# MotorDriver_Basic.net
KiCad netlist of a schematic drawn in EAGLE
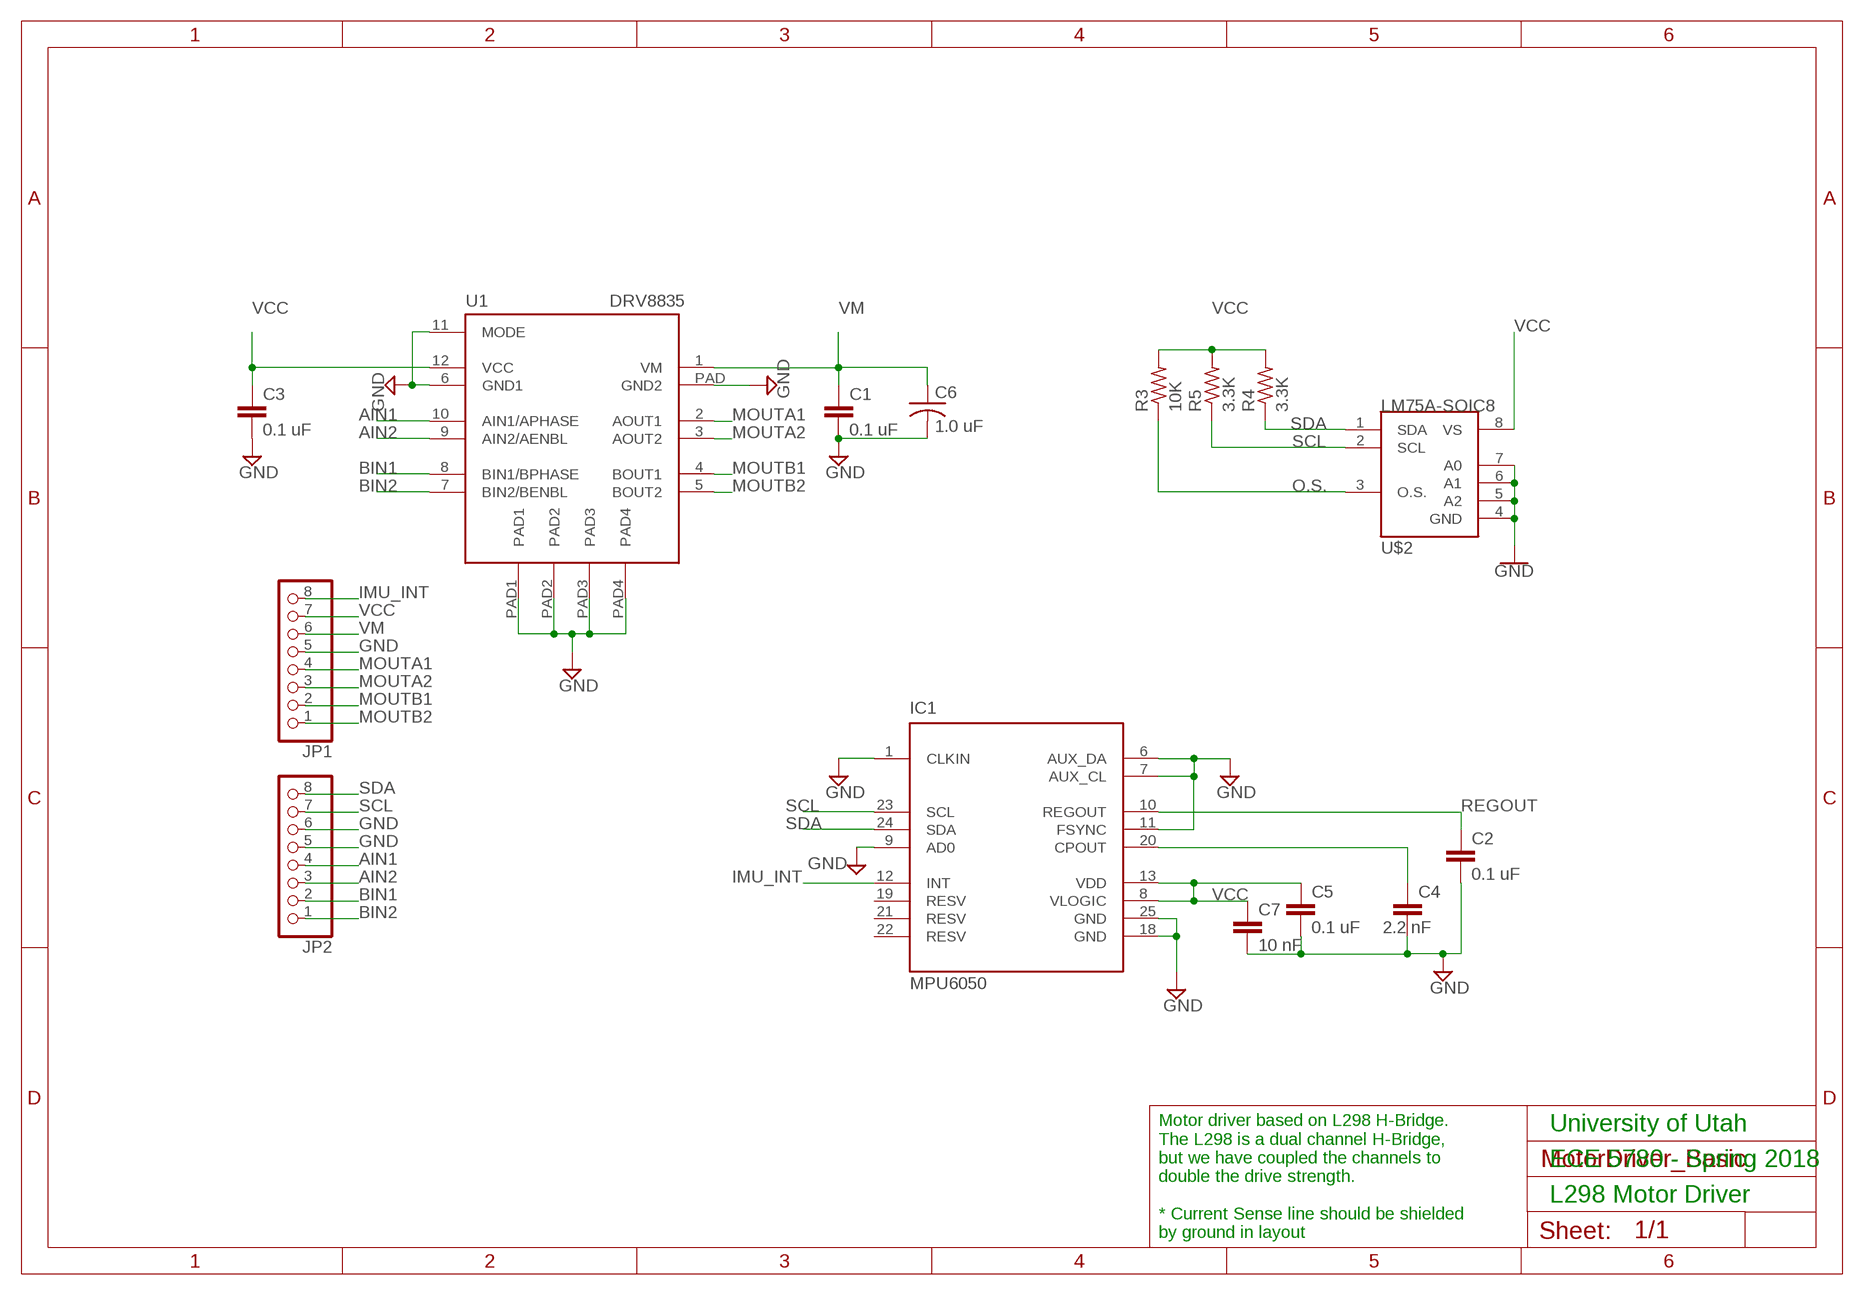
[diagram p0: schematic, sheet 1]

(export (version "E")
  (design (tool "Eeschema 10.0.6"))
  (components
    (comp (ref "C1")
      (value "0.1 uF")
      (footprint "eagle-import:C1206")
      (libsource (lib "eagle-import") (part "C-EUC1206"))
    )
    (comp (ref "C2")
      (value "0.1 uF")
      (footprint "eagle-import:C1206")
      (libsource (lib "eagle-import") (part "C-EUC1206"))
    )
    (comp (ref "C3")
      (value "0.1 uF")
      (footprint "eagle-import:C1206")
      (libsource (lib "eagle-import") (part "C-EUC1206"))
    )
    (comp (ref "C4")
      (value "2.2 nF")
      (footprint "eagle-import:C1206")
      (libsource (lib "eagle-import") (part "C-EUC1206"))
    )
    (comp (ref "C5")
      (value "0.1 uF")
      (footprint "eagle-import:C1206")
      (libsource (lib "eagle-import") (part "C-EUC1206"))
    )
    (comp (ref "C6")
      (value "1.0 uF")
      (footprint "eagle-import:C025-050X050")
      (libsource (lib "eagle-import") (part "C-US025-050X050"))
    )
    (comp (ref "C7")
      (value "10 nF")
      (footprint "eagle-import:C1206")
      (libsource (lib "eagle-import") (part "C-EUC1206"))
    )
    (comp (ref "IC1")
      (value "MPU6050")
      (footprint "eagle-import:QFN50P400X400X95-25T265X275N")
      (libsource (lib "eagle-import") (part "MPU6050"))
    )
    (comp (ref "JP1")
      (value "PINHD-1X8")
      (footprint "eagle-import:1X08")
      (libsource (lib "eagle-import") (part "PINHD-1X8"))
    )
    (comp (ref "JP2")
      (value "PINHD-1X8")
      (footprint "eagle-import:1X08")
      (libsource (lib "eagle-import") (part "PINHD-1X8"))
    )
    (comp (ref "R3")
      (value "10K")
      (footprint "eagle-import:M1206")
      (libsource (lib "eagle-import") (part "R-US_M1206"))
    )
    (comp (ref "R4")
      (value "3.3K")
      (footprint "eagle-import:M1206")
      (libsource (lib "eagle-import") (part "R-US_M1206"))
    )
    (comp (ref "R5")
      (value "3.3K")
      (footprint "eagle-import:M1206")
      (libsource (lib "eagle-import") (part "R-US_M1206"))
    )
    (comp (ref "U$2")
      (value "LM75A-SOIC8")
      (footprint "eagle-import:SOIC-8")
      (libsource (lib "eagle-import") (part "LM75A-SOIC8"))
    )
    (comp (ref "U1")
      (value "DRV8835")
      (footprint "eagle-import:WSON_2X3")
      (libsource (lib "eagle-import") (part "DRV8835"))
    )
  )
  (nets
    (net (code "1") (name "/AIN1") (class "Default")
      (node (ref "JP2") (pin "4") (pinfunction "4_4") (pintype "passive"))
      (node (ref "U1") (pin "10") (pinfunction "AIN1/APHASE_10") (pintype "bidirectional"))
    )
    (net (code "2") (name "/AIN2") (class "Default")
      (node (ref "JP2") (pin "3") (pinfunction "3_3") (pintype "passive"))
      (node (ref "U1") (pin "9") (pinfunction "AIN2/AENBL_9") (pintype "bidirectional"))
    )
    (net (code "3") (name "/BIN1") (class "Default")
      (node (ref "JP2") (pin "2") (pinfunction "2_2") (pintype "passive"))
      (node (ref "U1") (pin "8") (pinfunction "BIN1/BPHASE_8") (pintype "bidirectional"))
    )
    (net (code "4") (name "/BIN2") (class "Default")
      (node (ref "JP2") (pin "1") (pinfunction "1_1") (pintype "passive"))
      (node (ref "U1") (pin "7") (pinfunction "BIN2/BENBL_7") (pintype "bidirectional"))
    )
    (net (code "5") (name "/IMU_INT") (class "Default")
      (node (ref "IC1") (pin "12") (pinfunction "INT_12") (pintype "open_collector"))
      (node (ref "JP1") (pin "8") (pinfunction "8_8") (pintype "passive"))
    )
    (net (code "6") (name "/MOUTA1") (class "Default")
      (node (ref "JP1") (pin "4") (pinfunction "4_4") (pintype "passive"))
      (node (ref "U1") (pin "2") (pinfunction "AOUT1_2") (pintype "bidirectional"))
    )
    (net (code "7") (name "/MOUTA2") (class "Default")
      (node (ref "JP1") (pin "3") (pinfunction "3_3") (pintype "passive"))
      (node (ref "U1") (pin "3") (pinfunction "AOUT2_3") (pintype "bidirectional"))
    )
    (net (code "8") (name "/MOUTB1") (class "Default")
      (node (ref "JP1") (pin "2") (pinfunction "2_2") (pintype "passive"))
      (node (ref "U1") (pin "4") (pinfunction "BOUT1_4") (pintype "bidirectional"))
    )
    (net (code "9") (name "/MOUTB2") (class "Default")
      (node (ref "JP1") (pin "1") (pinfunction "1_1") (pintype "passive"))
      (node (ref "U1") (pin "5") (pinfunction "BOUT2_5") (pintype "bidirectional"))
    )
    (net (code "10") (name "/O.S.") (class "Default")
      (node (ref "R3") (pin "1") (pinfunction "1_1") (pintype "passive"))
      (node (ref "U$2") (pin "3") (pinfunction "O.S._3") (pintype "bidirectional"))
    )
    (net (code "11") (name "/REGOUT") (class "Default")
      (node (ref "C2") (pin "1") (pinfunction "1_1") (pintype "passive"))
      (node (ref "IC1") (pin "10") (pinfunction "REGOUT_10") (pintype "output"))
    )
    (net (code "12") (name "/SCL") (class "Default")
      (node (ref "IC1") (pin "23") (pinfunction "SCL_23") (pintype "input"))
      (node (ref "JP2") (pin "7") (pinfunction "7_7") (pintype "passive"))
      (node (ref "R5") (pin "1") (pinfunction "1_1") (pintype "passive"))
      (node (ref "U$2") (pin "2") (pinfunction "SCL_2") (pintype "bidirectional"))
    )
    (net (code "13") (name "/SDA") (class "Default")
      (node (ref "IC1") (pin "24") (pinfunction "SDA_24") (pintype "bidirectional"))
      (node (ref "JP2") (pin "8") (pinfunction "8_8") (pintype "passive"))
      (node (ref "R4") (pin "1") (pinfunction "1_1") (pintype "passive"))
      (node (ref "U$2") (pin "1") (pinfunction "SDA_1") (pintype "bidirectional"))
    )
    (net (code "14") (name "/VCC") (class "Default")
      (node (ref "C3") (pin "1") (pinfunction "1_1") (pintype "passive"))
      (node (ref "C5") (pin "1") (pinfunction "1_1") (pintype "passive"))
      (node (ref "C7") (pin "1") (pinfunction "1_1") (pintype "passive"))
      (node (ref "IC1") (pin "13") (pinfunction "VDD_13") (pintype "power_in"))
      (node (ref "IC1") (pin "8") (pinfunction "VLOGIC_8") (pintype "power_in"))
      (node (ref "JP1") (pin "7") (pinfunction "7_7") (pintype "passive"))
      (node (ref "R3") (pin "2") (pinfunction "2_2") (pintype "passive"))
      (node (ref "R4") (pin "2") (pinfunction "2_2") (pintype "passive"))
      (node (ref "R5") (pin "2") (pinfunction "2_2") (pintype "passive"))
      (node (ref "U$2") (pin "8") (pinfunction "VS_8") (pintype "bidirectional"))
      (node (ref "U1") (pin "12") (pinfunction "VCC_12") (pintype "bidirectional"))
    )
    (net (code "15") (name "/VM") (class "Default")
      (node (ref "C1") (pin "1") (pinfunction "1_1") (pintype "passive"))
      (node (ref "C6") (pin "1") (pinfunction "1_1") (pintype "passive"))
      (node (ref "JP1") (pin "6") (pinfunction "6_6") (pintype "passive"))
      (node (ref "U1") (pin "1") (pinfunction "VM_1") (pintype "bidirectional"))
    )
    (net (code "16") (name "GND") (class "Default")
      (node (ref "C1") (pin "2") (pinfunction "2_2") (pintype "passive"))
      (node (ref "C2") (pin "2") (pinfunction "2_2") (pintype "passive"))
      (node (ref "C3") (pin "2") (pinfunction "2_2") (pintype "passive"))
      (node (ref "C4") (pin "2") (pinfunction "2_2") (pintype "passive"))
      (node (ref "C5") (pin "2") (pinfunction "2_2") (pintype "passive"))
      (node (ref "C6") (pin "2") (pinfunction "2_2") (pintype "passive"))
      (node (ref "C7") (pin "2") (pinfunction "2_2") (pintype "passive"))
      (node (ref "IC1") (pin "1") (pinfunction "CLKIN_1") (pintype "input"))
      (node (ref "IC1") (pin "11") (pinfunction "FSYNC_11") (pintype "input"))
      (node (ref "IC1") (pin "18") (pinfunction "GND_18") (pintype "power_in"))
      (node (ref "IC1") (pin "25") (pinfunction "GND_25") (pintype "power_in"))
      (node (ref "IC1") (pin "6") (pinfunction "AUX_DA_6") (pintype "bidirectional"))
      (node (ref "IC1") (pin "7") (pinfunction "AUX_CL_7") (pintype "bidirectional"))
      (node (ref "IC1") (pin "9") (pinfunction "AD0_9") (pintype "input"))
      (node (ref "JP1") (pin "5") (pinfunction "5_5") (pintype "passive"))
      (node (ref "JP2") (pin "5") (pinfunction "5_5") (pintype "passive"))
      (node (ref "JP2") (pin "6") (pinfunction "6_6") (pintype "passive"))
      (node (ref "U$2") (pin "4") (pinfunction "GND_4") (pintype "bidirectional"))
      (node (ref "U$2") (pin "5") (pinfunction "A2_5") (pintype "bidirectional"))
      (node (ref "U$2") (pin "6") (pinfunction "A1_6") (pintype "bidirectional"))
      (node (ref "U$2") (pin "7") (pinfunction "A0_7") (pintype "bidirectional"))
      (node (ref "U1") (pin "11") (pinfunction "MODE_11") (pintype "bidirectional"))
      (node (ref "U1") (pin "6") (pinfunction "GND1_6") (pintype "bidirectional"))
      (node (ref "U1") (pin "PAD") (pinfunction "GND2_PAD") (pintype "bidirectional"))
      (node (ref "U1") (pin "PAD1") (pinfunction "PAD1_PAD1") (pintype "bidirectional"))
      (node (ref "U1") (pin "PAD2") (pinfunction "PAD2_PAD2") (pintype "bidirectional"))
      (node (ref "U1") (pin "PAD3") (pinfunction "PAD3_PAD3") (pintype "bidirectional"))
      (node (ref "U1") (pin "PAD4") (pinfunction "PAD4_PAD4") (pintype "bidirectional"))
    )
    (net (code "17") (name "Net-(IC1A-CPOUT)") (class "Default")
      (node (ref "C4") (pin "1") (pinfunction "1_1") (pintype "passive"))
      (node (ref "IC1") (pin "20") (pinfunction "CPOUT_20") (pintype "output"))
    )
    (net (code "18") (name "unconnected-(IC1A-RESV-Pad19)") (class "Default")
      (node (ref "IC1") (pin "19") (pinfunction "RESV_19") (pintype "passive"))
    )
    (net (code "19") (name "unconnected-(IC1A-RESV-Pad21)") (class "Default")
      (node (ref "IC1") (pin "21") (pinfunction "RESV_21") (pintype "passive"))
    )
    (net (code "20") (name "unconnected-(IC1A-RESV-Pad22)") (class "Default")
      (node (ref "IC1") (pin "22") (pinfunction "RESV_22") (pintype "passive"))
    )
  )
)
